# Battery_Charger.net
KiCad netlist of a schematic drawn in Altium Designer
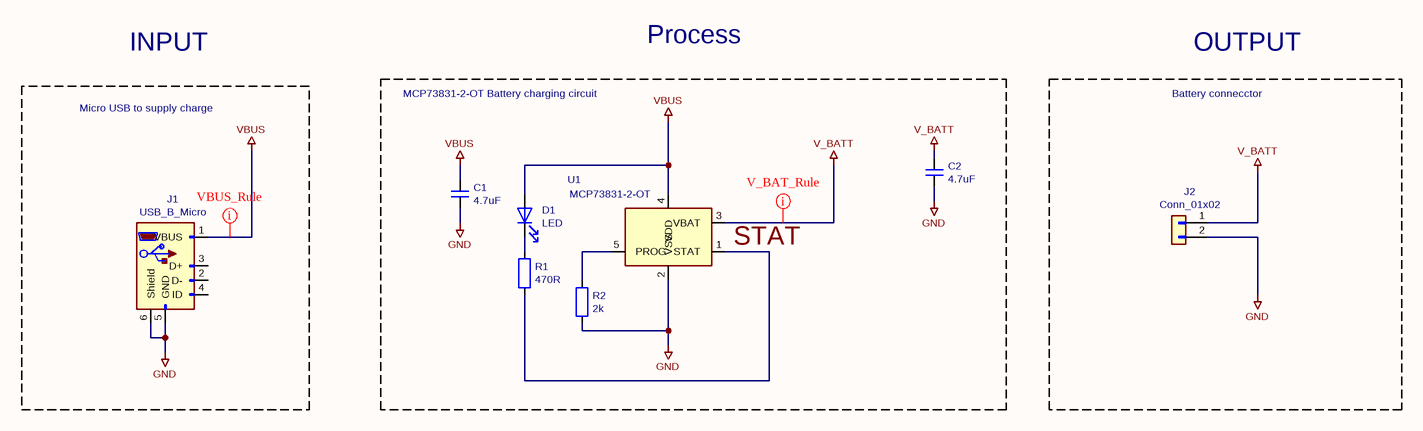
[diagram p0: Battery Charger.SchDoc]

(export (version "E")
  (design (tool "Eeschema 10.0.6"))
  (components
    (comp (ref "C1")
      (value "4.7uF")
      (footprint "C_1206_3216Metric_Pad1.42x1.75mm_HandSolder")
      (libsource (lib "Device") (part "C_Small"))
    )
    (comp (ref "C2")
      (value "4.7uF")
      (footprint "C_1206_3216Metric_Pad1.42x1.75mm_HandSolder")
      (libsource (lib "Device") (part "C_Small"))
    )
    (comp (ref "D1")
      (value "LED")
      (footprint "LED_1206_3216Metric_Pad1.42x1.75mm_HandSolder")
      (libsource (lib "Device") (part "LED"))
    )
    (comp (ref "J1")
      (value "USB_B_Micro")
      (footprint "USB_Micro-B_Molex-105017-0001")
      (libsource (lib "Connector") (part "USB_B_Micro"))
    )
    (comp (ref "J2")
      (value "Conn_01x02")
      (footprint "JST_GH_SM02B-GHS-TB_1x02-1MP_P1.25mm_Horizontal")
      (libsource (lib "Connector_Generic") (part "Conn_01x02"))
    )
    (comp (ref "R1")
      (value "470R")
      (footprint "R_1206_3216Metric_Pad1.42x1.75mm_HandSolder")
      (libsource (lib "Device") (part "R"))
    )
    (comp (ref "R2")
      (value "2k")
      (footprint "R_1206_3216Metric_Pad1.42x1.75mm_HandSolder")
      (libsource (lib "Device") (part "R"))
    )
    (comp (ref "U1")
      (value "MCP73831-2-OT")
      (footprint "SOT-23-5")
      (libsource (lib "Battery_Management") (part "MCP73831-2-OT"))
    )
  )
  (nets
    (net (code "1") (name "/STAT") (class "Default")
      (node (ref "R1") (pin "2") (pinfunction "2_2") (pintype "passive"))
      (node (ref "U1") (pin "1") (pinfunction "STAT_1") (pintype "passive"))
    )
    (net (code "2") (name "GND") (class "Default")
      (node (ref "C1") (pin "2") (pinfunction "2_2") (pintype "passive"))
      (node (ref "C2") (pin "2") (pinfunction "2_2") (pintype "passive"))
      (node (ref "J1") (pin "5") (pinfunction "GND_5") (pintype "passive"))
      (node (ref "J1") (pin "6") (pinfunction "Shield_6") (pintype "passive"))
      (node (ref "J2") (pin "2") (pinfunction "Pin_2_2") (pintype "passive"))
      (node (ref "R2") (pin "2") (pinfunction "2_2") (pintype "passive"))
      (node (ref "U1") (pin "2") (pinfunction "VSS_2") (pintype "passive"))
    )
    (net (code "3") (name "Net-(D1-K)") (class "Default")
      (node (ref "D1") (pin "1") (pinfunction "K_1") (pintype "passive"))
      (node (ref "R1") (pin "1") (pinfunction "1_1") (pintype "passive"))
    )
    (net (code "4") (name "Net-(U1-PROG)") (class "Default")
      (node (ref "R2") (pin "1") (pinfunction "1_1") (pintype "passive"))
      (node (ref "U1") (pin "5") (pinfunction "PROG_5") (pintype "passive"))
    )
    (net (code "5") (name "VBUS") (class "Default")
      (node (ref "C1") (pin "1") (pinfunction "1_1") (pintype "passive"))
      (node (ref "D1") (pin "2") (pinfunction "A_2") (pintype "passive"))
      (node (ref "J1") (pin "1") (pinfunction "VBUS_1") (pintype "passive"))
      (node (ref "U1") (pin "4") (pinfunction "VDD_4") (pintype "passive"))
    )
    (net (code "6") (name "V_BATT") (class "Default")
      (node (ref "C2") (pin "1") (pinfunction "1_1") (pintype "passive"))
      (node (ref "J2") (pin "1") (pinfunction "Pin_1_1") (pintype "passive"))
      (node (ref "U1") (pin "3") (pinfunction "VBAT_3") (pintype "passive"))
    )
    (net (code "7") (name "unconnected-(J1-D+-Pad3)") (class "Default")
      (node (ref "J1") (pin "3") (pinfunction "D+_3") (pintype "passive"))
    )
    (net (code "8") (name "unconnected-(J1-D--Pad2)") (class "Default")
      (node (ref "J1") (pin "2") (pinfunction "D-_2") (pintype "passive"))
    )
    (net (code "9") (name "unconnected-(J1-ID-Pad4)") (class "Default")
      (node (ref "J1") (pin "4") (pinfunction "ID_4") (pintype "passive"))
    )
  )
)
